# XE167FM.net
KiCad netlist of a schematic drawn in EAGLE
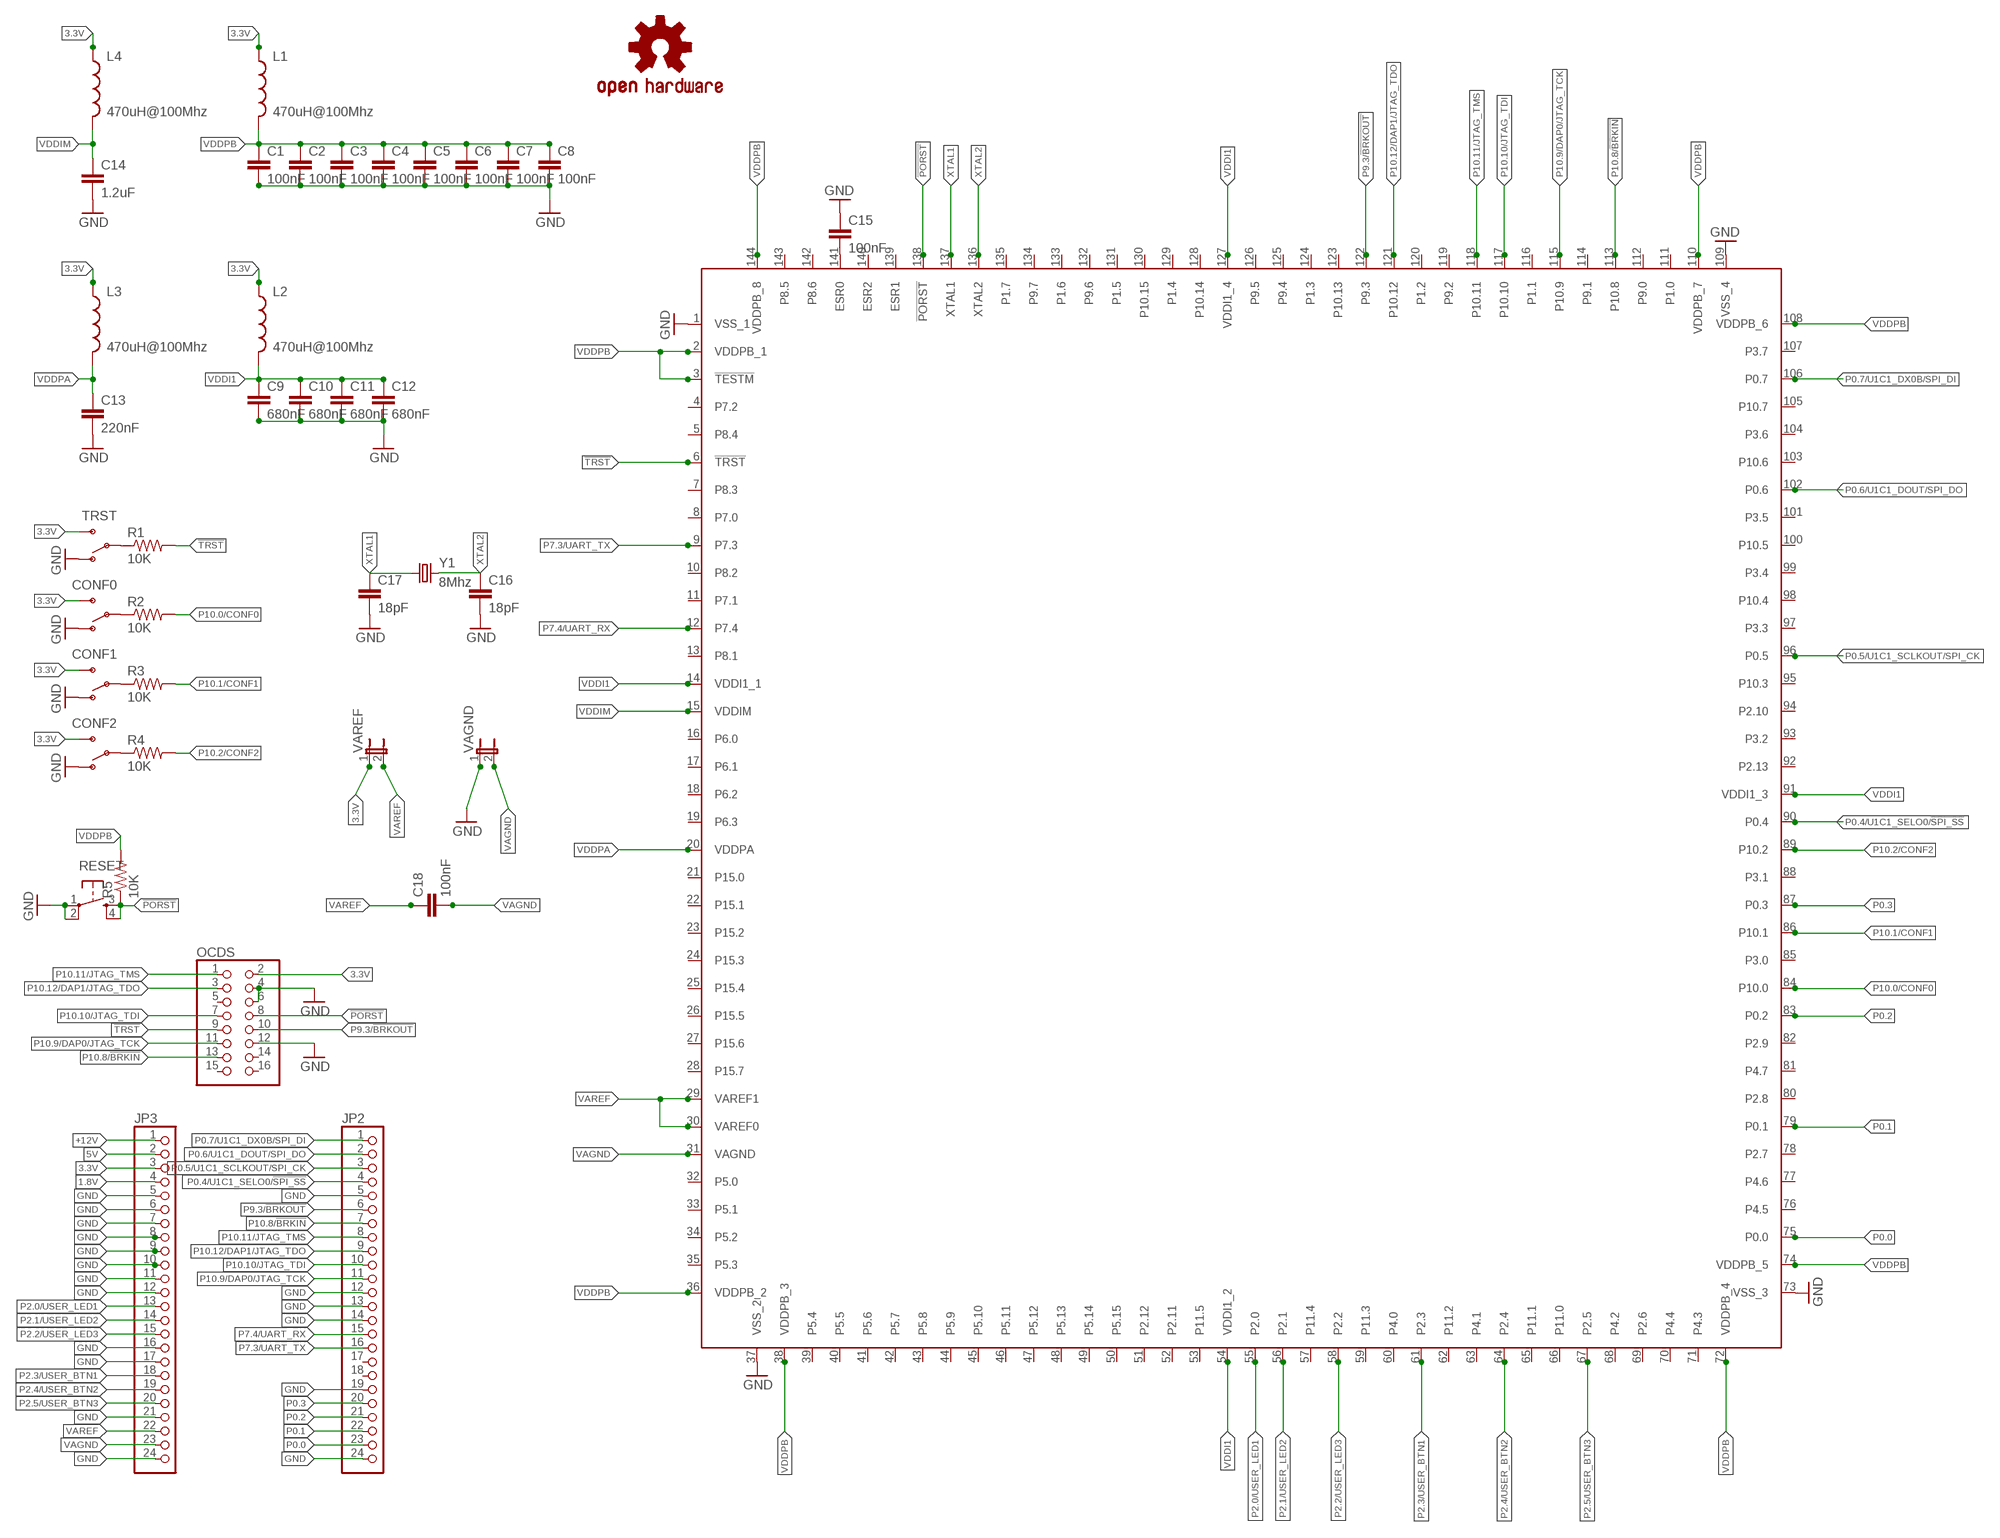
[diagram p0: schematic, sheet 1]

(export (version "E")
  (design (tool "Eeschema 10.0.6"))
  (components
    (comp (ref "C1")
      (value "100nF")
      (footprint "eagle-import:0603-CAP")
      (libsource (lib "eagle-import") (part "CAP0603-CAP"))
    )
    (comp (ref "C2")
      (value "100nF")
      (footprint "eagle-import:0603-CAP")
      (libsource (lib "eagle-import") (part "CAP0603-CAP"))
    )
    (comp (ref "C3")
      (value "100nF")
      (footprint "eagle-import:0603-CAP")
      (libsource (lib "eagle-import") (part "CAP0603-CAP"))
    )
    (comp (ref "C4")
      (value "100nF")
      (footprint "eagle-import:0603-CAP")
      (libsource (lib "eagle-import") (part "CAP0603-CAP"))
    )
    (comp (ref "C5")
      (value "100nF")
      (footprint "eagle-import:0603-CAP")
      (libsource (lib "eagle-import") (part "CAP0603-CAP"))
    )
    (comp (ref "C6")
      (value "100nF")
      (footprint "eagle-import:0603-CAP")
      (libsource (lib "eagle-import") (part "CAP0603-CAP"))
    )
    (comp (ref "C7")
      (value "100nF")
      (footprint "eagle-import:0603-CAP")
      (libsource (lib "eagle-import") (part "CAP0603-CAP"))
    )
    (comp (ref "C8")
      (value "100nF")
      (footprint "eagle-import:0603-CAP")
      (libsource (lib "eagle-import") (part "CAP0603-CAP"))
    )
    (comp (ref "C9")
      (value "680nF")
      (footprint "eagle-import:0603-CAP")
      (libsource (lib "eagle-import") (part "CAP0603-CAP"))
    )
    (comp (ref "C10")
      (value "680nF")
      (footprint "eagle-import:0603-CAP")
      (libsource (lib "eagle-import") (part "CAP0603-CAP"))
    )
    (comp (ref "C11")
      (value "680nF")
      (footprint "eagle-import:0603-CAP")
      (libsource (lib "eagle-import") (part "CAP0603-CAP"))
    )
    (comp (ref "C12")
      (value "680nF")
      (footprint "eagle-import:0603-CAP")
      (libsource (lib "eagle-import") (part "CAP0603-CAP"))
    )
    (comp (ref "C13")
      (value "220nF")
      (footprint "eagle-import:0603-CAP")
      (libsource (lib "eagle-import") (part "CAP0603-CAP"))
    )
    (comp (ref "C14")
      (value "1.2uF")
      (footprint "eagle-import:0603-CAP")
      (libsource (lib "eagle-import") (part "CAP0603-CAP"))
    )
    (comp (ref "C15")
      (value "100nF")
      (footprint "eagle-import:0603-CAP")
      (libsource (lib "eagle-import") (part "CAP0603-CAP"))
    )
    (comp (ref "C16")
      (value "18pF")
      (footprint "eagle-import:0603-CAP")
      (libsource (lib "eagle-import") (part "CAP0603-CAP"))
    )
    (comp (ref "C17")
      (value "18pF")
      (footprint "eagle-import:0603-CAP")
      (libsource (lib "eagle-import") (part "CAP0603-CAP"))
    )
    (comp (ref "C18")
      (value "100nF")
      (footprint "eagle-import:0603-CAP")
      (libsource (lib "eagle-import") (part "CAP0603-CAP"))
    )
    (comp (ref "CONF0")
      (value "SWITCH-SPDTPTH")
      (footprint "eagle-import:SWITCH-SPDT")
      (libsource (lib "eagle-import") (part "SWITCH-SPDTPTH"))
    )
    (comp (ref "CONF1")
      (value "SWITCH-SPDTPTH")
      (footprint "eagle-import:SWITCH-SPDT")
      (libsource (lib "eagle-import") (part "SWITCH-SPDTPTH"))
    )
    (comp (ref "CONF2")
      (value "SWITCH-SPDTPTH")
      (footprint "eagle-import:SWITCH-SPDT")
      (libsource (lib "eagle-import") (part "SWITCH-SPDTPTH"))
    )
    (comp (ref "IC1")
      (value "XE167FM")
      (footprint "eagle-import:LQFP144")
      (libsource (lib "eagle-import") (part "XE167FM"))
    )
    (comp (ref "JP2")
      (value "PINHD-1X24")
      (footprint "eagle-import:1X24")
      (libsource (lib "eagle-import") (part "PINHD-1X24"))
    )
    (comp (ref "JP3")
      (value "PINHD-1X24")
      (footprint "eagle-import:1X24")
      (libsource (lib "eagle-import") (part "PINHD-1X24"))
    )
    (comp (ref "L1")
      (value "470uH@100Mhz")
      (footprint "eagle-import:0603")
      (libsource (lib "eagle-import") (part "INDUCTOR0603"))
    )
    (comp (ref "L2")
      (value "470uH@100Mhz")
      (footprint "eagle-import:0603")
      (libsource (lib "eagle-import") (part "INDUCTOR0603"))
    )
    (comp (ref "L3")
      (value "470uH@100Mhz")
      (footprint "eagle-import:0603")
      (libsource (lib "eagle-import") (part "INDUCTOR0603"))
    )
    (comp (ref "L4")
      (value "470uH@100Mhz")
      (footprint "eagle-import:0603")
      (libsource (lib "eagle-import") (part "INDUCTOR0603"))
    )
    (comp (ref "LOGO1")
      (value "OSHW-LOGOS")
      (footprint "eagle-import:OSHW-LOGO-S")
      (libsource (lib "eagle-import") (part "OSHW-LOGOS"))
    )
    (comp (ref "OCDS")
      (value "PINHD-2X8_2.54")
      (footprint "eagle-import:2X08")
      (libsource (lib "eagle-import") (part "PINHD-2X8_2.54"))
    )
    (comp (ref "R1")
      (value "10K")
      (footprint "eagle-import:0603-RES")
      (libsource (lib "eagle-import") (part "RESISTOR0603-RES"))
    )
    (comp (ref "R2")
      (value "10K")
      (footprint "eagle-import:0603-RES")
      (libsource (lib "eagle-import") (part "RESISTOR0603-RES"))
    )
    (comp (ref "R3")
      (value "10K")
      (footprint "eagle-import:0603-RES")
      (libsource (lib "eagle-import") (part "RESISTOR0603-RES"))
    )
    (comp (ref "R4")
      (value "10K")
      (footprint "eagle-import:0603-RES")
      (libsource (lib "eagle-import") (part "RESISTOR0603-RES"))
    )
    (comp (ref "R5")
      (value "10K")
      (footprint "eagle-import:0603-RES")
      (libsource (lib "eagle-import") (part "RESISTOR0603-RES"))
    )
    (comp (ref "RESET")
      (value "TAC_SWITCHPTH")
      (footprint "eagle-import:TACTILE-PTH")
      (libsource (lib "eagle-import") (part "TAC_SWITCHPTH"))
    )
    (comp (ref "TRST")
      (value "SWITCH-SPDTPTH")
      (footprint "eagle-import:SWITCH-SPDT")
      (libsource (lib "eagle-import") (part "SWITCH-SPDTPTH"))
    )
    (comp (ref "VAGND")
      (value "JP1E")
      (footprint "eagle-import:JP1")
      (libsource (lib "eagle-import") (part "JP1E"))
    )
    (comp (ref "VAREF")
      (value "JP1E")
      (footprint "eagle-import:JP1")
      (libsource (lib "eagle-import") (part "JP1E"))
    )
    (comp (ref "Y1")
      (value "8Mhz")
      (footprint "eagle-import:HC49UP")
      (libsource (lib "eagle-import") (part "CRYSTALSMD"))
    )
  )
  (nets
    (net (code "1") (name "+12V") (class "Default")
      (node (ref "JP3") (pin "1") (pinfunction "1_1") (pintype "passive"))
    )
    (net (code "2") (name "/P0.4{slash}U1C1_SELO0{slash}~{SPI_SS}") (class "Default")
      (node (ref "IC1") (pin "90") (pinfunction "P0.4_90") (pintype "passive"))
      (node (ref "JP2") (pin "4") (pinfunction "4_4") (pintype "passive"))
    )
    (net (code "3") (name "/P9.3{slash}~{BRKOUT}") (class "Default")
      (node (ref "IC1") (pin "122") (pinfunction "P9.3_122") (pintype "passive"))
      (node (ref "JP2") (pin "6") (pinfunction "6_6") (pintype "passive"))
      (node (ref "OCDS") (pin "10") (pinfunction "10_10") (pintype "passive"))
    )
    (net (code "4") (name "/P10.8{slash}~{BRKIN}") (class "Default")
      (node (ref "IC1") (pin "113") (pinfunction "P10.8_113") (pintype "passive"))
      (node (ref "JP2") (pin "7") (pinfunction "7_7") (pintype "passive"))
      (node (ref "OCDS") (pin "13") (pinfunction "13_13") (pintype "passive"))
    )
    (net (code "5") (name "/~{PORST}") (class "Default")
      (node (ref "IC1") (pin "138") (pinfunction "~{PORST}_138") (pintype "passive"))
      (node (ref "OCDS") (pin "8") (pinfunction "8_8") (pintype "passive"))
      (node (ref "R5") (pin "1") (pinfunction "1_1") (pintype "passive"))
      (node (ref "RESET") (pin "3") (pinfunction "3_3") (pintype "passive"))
      (node (ref "RESET") (pin "4") (pinfunction "4_4") (pintype "passive"))
    )
    (net (code "6") (name "/~{TRST}") (class "Default")
      (node (ref "IC1") (pin "6") (pinfunction "~{TRST}_6") (pintype "passive"))
      (node (ref "OCDS") (pin "9") (pinfunction "9_9") (pintype "passive"))
      (node (ref "R1") (pin "2") (pinfunction "2_2") (pintype "passive"))
    )
    (net (code "7") (name "1.8V") (class "Default")
      (node (ref "JP3") (pin "4") (pinfunction "4_4") (pintype "passive"))
    )
    (net (code "8") (name "3.3V") (class "Default")
      (node (ref "CONF0") (pin "3") (pinfunction "S_3") (pintype "passive"))
      (node (ref "CONF1") (pin "3") (pinfunction "S_3") (pintype "passive"))
      (node (ref "CONF2") (pin "3") (pinfunction "S_3") (pintype "passive"))
      (node (ref "JP3") (pin "3") (pinfunction "3_3") (pintype "passive"))
      (node (ref "L1") (pin "1") (pinfunction "1_1") (pintype "passive"))
      (node (ref "L2") (pin "1") (pinfunction "1_1") (pintype "passive"))
      (node (ref "L3") (pin "1") (pinfunction "1_1") (pintype "passive"))
      (node (ref "L4") (pin "1") (pinfunction "1_1") (pintype "passive"))
      (node (ref "OCDS") (pin "2") (pinfunction "2_2") (pintype "passive"))
      (node (ref "TRST") (pin "3") (pinfunction "S_3") (pintype "passive"))
      (node (ref "VAREF") (pin "1") (pinfunction "1_1") (pintype "passive"))
    )
    (net (code "9") (name "5V") (class "Default")
      (node (ref "JP3") (pin "2") (pinfunction "2_2") (pintype "passive"))
    )
    (net (code "10") (name "GND") (class "Default")
      (node (ref "C1") (pin "2") (pinfunction "2_2") (pintype "passive"))
      (node (ref "C10") (pin "2") (pinfunction "2_2") (pintype "passive"))
      (node (ref "C11") (pin "2") (pinfunction "2_2") (pintype "passive"))
      (node (ref "C12") (pin "2") (pinfunction "2_2") (pintype "passive"))
      (node (ref "C13") (pin "2") (pinfunction "2_2") (pintype "passive"))
      (node (ref "C14") (pin "2") (pinfunction "2_2") (pintype "passive"))
      (node (ref "C15") (pin "1") (pinfunction "1_1") (pintype "passive"))
      (node (ref "C16") (pin "2") (pinfunction "2_2") (pintype "passive"))
      (node (ref "C17") (pin "2") (pinfunction "2_2") (pintype "passive"))
      (node (ref "C2") (pin "2") (pinfunction "2_2") (pintype "passive"))
      (node (ref "C3") (pin "2") (pinfunction "2_2") (pintype "passive"))
      (node (ref "C4") (pin "2") (pinfunction "2_2") (pintype "passive"))
      (node (ref "C5") (pin "2") (pinfunction "2_2") (pintype "passive"))
      (node (ref "C6") (pin "2") (pinfunction "2_2") (pintype "passive"))
      (node (ref "C7") (pin "2") (pinfunction "2_2") (pintype "passive"))
      (node (ref "C8") (pin "2") (pinfunction "2_2") (pintype "passive"))
      (node (ref "C9") (pin "2") (pinfunction "2_2") (pintype "passive"))
      (node (ref "CONF0") (pin "1") (pinfunction "O_1") (pintype "passive"))
      (node (ref "CONF1") (pin "1") (pinfunction "O_1") (pintype "passive"))
      (node (ref "CONF2") (pin "1") (pinfunction "O_1") (pintype "passive"))
      (node (ref "IC1") (pin "1") (pinfunction "VSS_1_1") (pintype "passive"))
      (node (ref "IC1") (pin "109") (pinfunction "VSS_4_109") (pintype "passive"))
      (node (ref "IC1") (pin "37") (pinfunction "VSS_2_37") (pintype "passive"))
      (node (ref "IC1") (pin "73") (pinfunction "VSS_3_73") (pintype "passive"))
      (node (ref "JP2") (pin "12") (pinfunction "12_12") (pintype "passive"))
      (node (ref "JP2") (pin "13") (pinfunction "13_13") (pintype "passive"))
      (node (ref "JP2") (pin "14") (pinfunction "14_14") (pintype "passive"))
      (node (ref "JP2") (pin "19") (pinfunction "19_19") (pintype "passive"))
      (node (ref "JP2") (pin "24") (pinfunction "24_24") (pintype "passive"))
      (node (ref "JP2") (pin "5") (pinfunction "5_5") (pintype "passive"))
      (node (ref "JP3") (pin "10") (pinfunction "10_10") (pintype "passive"))
      (node (ref "JP3") (pin "11") (pinfunction "11_11") (pintype "passive"))
      (node (ref "JP3") (pin "12") (pinfunction "12_12") (pintype "passive"))
      (node (ref "JP3") (pin "16") (pinfunction "16_16") (pintype "passive"))
      (node (ref "JP3") (pin "17") (pinfunction "17_17") (pintype "passive"))
      (node (ref "JP3") (pin "21") (pinfunction "21_21") (pintype "passive"))
      (node (ref "JP3") (pin "24") (pinfunction "24_24") (pintype "passive"))
      (node (ref "JP3") (pin "5") (pinfunction "5_5") (pintype "passive"))
      (node (ref "JP3") (pin "6") (pinfunction "6_6") (pintype "passive"))
      (node (ref "JP3") (pin "7") (pinfunction "7_7") (pintype "passive"))
      (node (ref "JP3") (pin "8") (pinfunction "8_8") (pintype "passive"))
      (node (ref "JP3") (pin "9") (pinfunction "9_9") (pintype "passive"))
      (node (ref "OCDS") (pin "12") (pinfunction "12_12") (pintype "passive"))
      (node (ref "OCDS") (pin "4") (pinfunction "4_4") (pintype "passive"))
      (node (ref "OCDS") (pin "6") (pinfunction "6_6") (pintype "passive"))
      (node (ref "RESET") (pin "1") (pinfunction "1_1") (pintype "passive"))
      (node (ref "RESET") (pin "2") (pinfunction "2_2") (pintype "passive"))
      (node (ref "TRST") (pin "1") (pinfunction "O_1") (pintype "passive"))
      (node (ref "VAGND") (pin "1") (pinfunction "1_1") (pintype "passive"))
    )
    (net (code "11") (name "Net-(CONF0-P)") (class "Default")
      (node (ref "CONF0") (pin "2") (pinfunction "P_2") (pintype "passive"))
      (node (ref "R2") (pin "1") (pinfunction "1_1") (pintype "passive"))
    )
    (net (code "12") (name "Net-(CONF1-P)") (class "Default")
      (node (ref "CONF1") (pin "2") (pinfunction "P_2") (pintype "passive"))
      (node (ref "R3") (pin "1") (pinfunction "1_1") (pintype "passive"))
    )
    (net (code "13") (name "Net-(CONF2-P)") (class "Default")
      (node (ref "CONF2") (pin "2") (pinfunction "P_2") (pintype "passive"))
      (node (ref "R4") (pin "1") (pinfunction "1_1") (pintype "passive"))
    )
    (net (code "14") (name "Net-(IC1-ESR0)") (class "Default")
      (node (ref "C15") (pin "2") (pinfunction "2_2") (pintype "passive"))
      (node (ref "IC1") (pin "141") (pinfunction "ESR0_141") (pintype "passive"))
    )
    (net (code "15") (name "Net-(TRST-P)") (class "Default")
      (node (ref "R1") (pin "1") (pinfunction "1_1") (pintype "passive"))
      (node (ref "TRST") (pin "2") (pinfunction "P_2") (pintype "passive"))
    )
    (net (code "16") (name "P0.0") (class "Default")
      (node (ref "IC1") (pin "75") (pinfunction "P0.0_75") (pintype "passive"))
      (node (ref "JP2") (pin "23") (pinfunction "23_23") (pintype "passive"))
    )
    (net (code "17") (name "P0.1") (class "Default")
      (node (ref "IC1") (pin "79") (pinfunction "P0.1_79") (pintype "passive"))
      (node (ref "JP2") (pin "22") (pinfunction "22_22") (pintype "passive"))
    )
    (net (code "18") (name "P0.2") (class "Default")
      (node (ref "IC1") (pin "83") (pinfunction "P0.2_83") (pintype "passive"))
      (node (ref "JP2") (pin "21") (pinfunction "21_21") (pintype "passive"))
    )
    (net (code "19") (name "P0.3") (class "Default")
      (node (ref "IC1") (pin "87") (pinfunction "P0.3_87") (pintype "passive"))
      (node (ref "JP2") (pin "20") (pinfunction "20_20") (pintype "passive"))
    )
    (net (code "20") (name "P0.5{slash}U1C1_SCLKOUT{slash}SPI_CK") (class "Default")
      (node (ref "IC1") (pin "96") (pinfunction "P0.5_96") (pintype "passive"))
      (node (ref "JP2") (pin "3") (pinfunction "3_3") (pintype "passive"))
    )
    (net (code "21") (name "P0.6{slash}U1C1_DOUT{slash}SPI_DO") (class "Default")
      (node (ref "IC1") (pin "102") (pinfunction "P0.6_102") (pintype "passive"))
      (node (ref "JP2") (pin "2") (pinfunction "2_2") (pintype "passive"))
    )
    (net (code "22") (name "P0.7{slash}U1C1_DX0B{slash}SPI_DI") (class "Default")
      (node (ref "IC1") (pin "106") (pinfunction "P0.7_106") (pintype "passive"))
      (node (ref "JP2") (pin "1") (pinfunction "1_1") (pintype "passive"))
    )
    (net (code "23") (name "P2.0{slash}USER_LED1") (class "Default")
      (node (ref "IC1") (pin "55") (pinfunction "P2.0_55") (pintype "passive"))
      (node (ref "JP3") (pin "13") (pinfunction "13_13") (pintype "passive"))
    )
    (net (code "24") (name "P2.1{slash}USER_LED2") (class "Default")
      (node (ref "IC1") (pin "56") (pinfunction "P2.1_56") (pintype "passive"))
      (node (ref "JP3") (pin "14") (pinfunction "14_14") (pintype "passive"))
    )
    (net (code "25") (name "P2.2{slash}USER_LED3") (class "Default")
      (node (ref "IC1") (pin "58") (pinfunction "P2.2_58") (pintype "passive"))
      (node (ref "JP3") (pin "15") (pinfunction "15_15") (pintype "passive"))
    )
    (net (code "26") (name "P2.3{slash}USER_BTN1") (class "Default")
      (node (ref "IC1") (pin "61") (pinfunction "P2.3_61") (pintype "passive"))
      (node (ref "JP3") (pin "18") (pinfunction "18_18") (pintype "passive"))
    )
    (net (code "27") (name "P2.4{slash}USER_BTN2") (class "Default")
      (node (ref "IC1") (pin "64") (pinfunction "P2.4_64") (pintype "passive"))
      (node (ref "JP3") (pin "19") (pinfunction "19_19") (pintype "passive"))
    )
    (net (code "28") (name "P2.5{slash}USER_BTN3") (class "Default")
      (node (ref "IC1") (pin "67") (pinfunction "P2.5_67") (pintype "passive"))
      (node (ref "JP3") (pin "20") (pinfunction "20_20") (pintype "passive"))
    )
    (net (code "29") (name "P7.3{slash}UART_TX") (class "Default")
      (node (ref "IC1") (pin "9") (pinfunction "P7.3_9") (pintype "passive"))
      (node (ref "JP2") (pin "16") (pinfunction "16_16") (pintype "passive"))
    )
    (net (code "30") (name "P7.4{slash}UART_RX") (class "Default")
      (node (ref "IC1") (pin "12") (pinfunction "P7.4_12") (pintype "passive"))
      (node (ref "JP2") (pin "15") (pinfunction "15_15") (pintype "passive"))
    )
    (net (code "31") (name "P10.0{slash}CONF0") (class "Default")
      (node (ref "IC1") (pin "84") (pinfunction "P10.0_84") (pintype "passive"))
      (node (ref "R2") (pin "2") (pinfunction "2_2") (pintype "passive"))
    )
    (net (code "32") (name "P10.1{slash}CONF1") (class "Default")
      (node (ref "IC1") (pin "86") (pinfunction "P10.1_86") (pintype "passive"))
      (node (ref "R3") (pin "2") (pinfunction "2_2") (pintype "passive"))
    )
    (net (code "33") (name "P10.2{slash}CONF2") (class "Default")
      (node (ref "IC1") (pin "89") (pinfunction "P10.2_89") (pintype "passive"))
      (node (ref "R4") (pin "2") (pinfunction "2_2") (pintype "passive"))
    )
    (net (code "34") (name "P10.9{slash}DAP0{slash}JTAG_TCK") (class "Default")
      (node (ref "IC1") (pin "115") (pinfunction "P10.9_115") (pintype "passive"))
      (node (ref "JP2") (pin "11") (pinfunction "11_11") (pintype "passive"))
      (node (ref "OCDS") (pin "11") (pinfunction "11_11") (pintype "passive"))
    )
    (net (code "35") (name "P10.10{slash}JTAG_TDI") (class "Default")
      (node (ref "IC1") (pin "117") (pinfunction "P10.10_117") (pintype "passive"))
      (node (ref "JP2") (pin "10") (pinfunction "10_10") (pintype "passive"))
      (node (ref "OCDS") (pin "7") (pinfunction "7_7") (pintype "passive"))
    )
    (net (code "36") (name "P10.11{slash}JTAG_TMS") (class "Default")
      (node (ref "IC1") (pin "118") (pinfunction "P10.11_118") (pintype "passive"))
      (node (ref "JP2") (pin "8") (pinfunction "8_8") (pintype "passive"))
      (node (ref "OCDS") (pin "1") (pinfunction "1_1") (pintype "passive"))
    )
    (net (code "37") (name "P10.12{slash}DAP1{slash}JTAG_TDO") (class "Default")
      (node (ref "IC1") (pin "121") (pinfunction "P10.12_121") (pintype "passive"))
      (node (ref "JP2") (pin "9") (pinfunction "9_9") (pintype "passive"))
      (node (ref "OCDS") (pin "3") (pinfunction "3_3") (pintype "passive"))
    )
    (net (code "38") (name "VAGND") (class "Default")
      (node (ref "C18") (pin "2") (pinfunction "2_2") (pintype "passive"))
      (node (ref "IC1") (pin "31") (pinfunction "VAGND_31") (pintype "passive"))
      (node (ref "JP3") (pin "23") (pinfunction "23_23") (pintype "passive"))
      (node (ref "VAGND") (pin "2") (pinfunction "2_2") (pintype "passive"))
    )
    (net (code "39") (name "VAREF") (class "Default")
      (node (ref "C18") (pin "1") (pinfunction "1_1") (pintype "passive"))
      (node (ref "IC1") (pin "29") (pinfunction "VAREF1_29") (pintype "passive"))
      (node (ref "IC1") (pin "30") (pinfunction "VAREF0_30") (pintype "passive"))
      (node (ref "JP3") (pin "22") (pinfunction "22_22") (pintype "passive"))
      (node (ref "VAREF") (pin "2") (pinfunction "2_2") (pintype "passive"))
    )
    (net (code "40") (name "VDDI1") (class "Default")
      (node (ref "C10") (pin "1") (pinfunction "1_1") (pintype "passive"))
      (node (ref "C11") (pin "1") (pinfunction "1_1") (pintype "passive"))
      (node (ref "C12") (pin "1") (pinfunction "1_1") (pintype "passive"))
      (node (ref "C9") (pin "1") (pinfunction "1_1") (pintype "passive"))
      (node (ref "IC1") (pin "127") (pinfunction "VDDI1_4_127") (pintype "passive"))
      (node (ref "IC1") (pin "14") (pinfunction "VDDI1_1_14") (pintype "passive"))
      (node (ref "IC1") (pin "54") (pinfunction "VDDI1_2_54") (pintype "passive"))
      (node (ref "IC1") (pin "91") (pinfunction "VDDI1_3_91") (pintype "passive"))
      (node (ref "L2") (pin "2") (pinfunction "2_2") (pintype "passive"))
    )
    (net (code "41") (name "VDDIM") (class "Default")
      (node (ref "C14") (pin "1") (pinfunction "1_1") (pintype "passive"))
      (node (ref "IC1") (pin "15") (pinfunction "VDDIM_15") (pintype "passive"))
      (node (ref "L4") (pin "2") (pinfunction "2_2") (pintype "passive"))
    )
    (net (code "42") (name "VDDPA") (class "Default")
      (node (ref "C13") (pin "1") (pinfunction "1_1") (pintype "passive"))
      (node (ref "IC1") (pin "20") (pinfunction "VDDPA_20") (pintype "passive"))
      (node (ref "L3") (pin "2") (pinfunction "2_2") (pintype "passive"))
    )
    (net (code "43") (name "VDDPB") (class "Default")
      (node (ref "C1") (pin "1") (pinfunction "1_1") (pintype "passive"))
      (node (ref "C2") (pin "1") (pinfunction "1_1") (pintype "passive"))
      (node (ref "C3") (pin "1") (pinfunction "1_1") (pintype "passive"))
      (node (ref "C4") (pin "1") (pinfunction "1_1") (pintype "passive"))
      (node (ref "C5") (pin "1") (pinfunction "1_1") (pintype "passive"))
      (node (ref "C6") (pin "1") (pinfunction "1_1") (pintype "passive"))
      (node (ref "C7") (pin "1") (pinfunction "1_1") (pintype "passive"))
      (node (ref "C8") (pin "1") (pinfunction "1_1") (pintype "passive"))
      (node (ref "IC1") (pin "108") (pinfunction "VDDPB_6_108") (pintype "passive"))
      (node (ref "IC1") (pin "110") (pinfunction "VDDPB_7_110") (pintype "passive"))
      (node (ref "IC1") (pin "144") (pinfunction "VDDPB_8_144") (pintype "passive"))
      (node (ref "IC1") (pin "2") (pinfunction "VDDPB_1_2") (pintype "passive"))
      (node (ref "IC1") (pin "3") (pinfunction "~{TESTM}_3") (pintype "passive"))
      (node (ref "IC1") (pin "36") (pinfunction "VDDPB_2_36") (pintype "passive"))
      (node (ref "IC1") (pin "38") (pinfunction "VDDPB_3_38") (pintype "passive"))
      (node (ref "IC1") (pin "72") (pinfunction "VDDPB_4_72") (pintype "passive"))
      (node (ref "IC1") (pin "74") (pinfunction "VDDPB_5_74") (pintype "passive"))
      (node (ref "L1") (pin "2") (pinfunction "2_2") (pintype "passive"))
      (node (ref "R5") (pin "2") (pinfunction "2_2") (pintype "passive"))
    )
    (net (code "44") (name "XTAL1") (class "Default")
      (node (ref "C17") (pin "1") (pinfunction "1_1") (pintype "passive"))
      (node (ref "IC1") (pin "137") (pinfunction "XTAL1_137") (pintype "passive"))
      (node (ref "Y1") (pin "1") (pinfunction "1_1") (pintype "passive"))
    )
    (net (code "45") (name "XTAL2") (class "Default")
      (node (ref "C16") (pin "1") (pinfunction "1_1") (pintype "passive"))
      (node (ref "IC1") (pin "136") (pinfunction "XTAL2_136") (pintype "passive"))
      (node (ref "Y1") (pin "2") (pinfunction "2_2") (pintype "passive"))
    )
    (net (code "46") (name "unconnected-(IC1-ESR1-Pad139)") (class "Default")
      (node (ref "IC1") (pin "139") (pinfunction "ESR1_139") (pintype "passive"))
    )
    (net (code "47") (name "unconnected-(IC1-ESR2-Pad140)") (class "Default")
      (node (ref "IC1") (pin "140") (pinfunction "ESR2_140") (pintype "passive"))
    )
    (net (code "48") (name "unconnected-(IC1-P1.0-Pad111)") (class "Default")
      (node (ref "IC1") (pin "111") (pinfunction "P1.0_111") (pintype "passive"))
    )
    (net (code "49") (name "unconnected-(IC1-P1.1-Pad116)") (class "Default")
      (node (ref "IC1") (pin "116") (pinfunction "P1.1_116") (pintype "passive"))
    )
    (net (code "50") (name "unconnected-(IC1-P1.2-Pad120)") (class "Default")
      (node (ref "IC1") (pin "120") (pinfunction "P1.2_120") (pintype "passive"))
    )
    (net (code "51") (name "unconnected-(IC1-P1.3-Pad124)") (class "Default")
      (node (ref "IC1") (pin "124") (pinfunction "P1.3_124") (pintype "passive"))
    )
    (net (code "52") (name "unconnected-(IC1-P1.4-Pad129)") (class "Default")
      (node (ref "IC1") (pin "129") (pinfunction "P1.4_129") (pintype "passive"))
    )
    (net (code "53") (name "unconnected-(IC1-P1.5-Pad131)") (class "Default")
      (node (ref "IC1") (pin "131") (pinfunction "P1.5_131") (pintype "passive"))
    )
    (net (code "54") (name "unconnected-(IC1-P1.6-Pad133)") (class "Default")
      (node (ref "IC1") (pin "133") (pinfunction "P1.6_133") (pintype "passive"))
    )
    (net (code "55") (name "unconnected-(IC1-P1.7-Pad135)") (class "Default")
      (node (ref "IC1") (pin "135") (pinfunction "P1.7_135") (pintype "passive"))
    )
    (net (code "56") (name "unconnected-(IC1-P2.6-Pad69)") (class "Default")
      (node (ref "IC1") (pin "69") (pinfunction "P2.6_69") (pintype "passive"))
    )
    (net (code "57") (name "unconnected-(IC1-P2.7-Pad78)") (class "Default")
      (node (ref "IC1") (pin "78") (pinfunction "P2.7_78") (pintype "passive"))
    )
    (net (code "58") (name "unconnected-(IC1-P2.8-Pad80)") (class "Default")
      (node (ref "IC1") (pin "80") (pinfunction "P2.8_80") (pintype "passive"))
    )
    (net (code "59") (name "unconnected-(IC1-P2.9-Pad82)") (class "Default")
      (node (ref "IC1") (pin "82") (pinfunction "P2.9_82") (pintype "passive"))
    )
    (net (code "60") (name "unconnected-(IC1-P2.10-Pad94)") (class "Default")
      (node (ref "IC1") (pin "94") (pinfunction "P2.10_94") (pintype "passive"))
    )
    (net (code "61") (name "unconnected-(IC1-P2.11-Pad52)") (class "Default")
      (node (ref "IC1") (pin "52") (pinfunction "P2.11_52") (pintype "passive"))
    )
    (net (code "62") (name "unconnected-(IC1-P2.12-Pad51)") (class "Default")
      (node (ref "IC1") (pin "51") (pinfunction "P2.12_51") (pintype "passive"))
    )
    (net (code "63") (name "unconnected-(IC1-P2.13-Pad92)") (class "Default")
      (node (ref "IC1") (pin "92") (pinfunction "P2.13_92") (pintype "passive"))
    )
    (net (code "64") (name "unconnected-(IC1-P3.0-Pad85)") (class "Default")
      (node (ref "IC1") (pin "85") (pinfunction "P3.0_85") (pintype "passive"))
    )
    (net (code "65") (name "unconnected-(IC1-P3.1-Pad88)") (class "Default")
      (node (ref "IC1") (pin "88") (pinfunction "P3.1_88") (pintype "passive"))
    )
    (net (code "66") (name "unconnected-(IC1-P3.2-Pad93)") (class "Default")
      (node (ref "IC1") (pin "93") (pinfunction "P3.2_93") (pintype "passive"))
    )
    (net (code "67") (name "unconnected-(IC1-P3.3-Pad97)") (class "Default")
      (node (ref "IC1") (pin "97") (pinfunction "P3.3_97") (pintype "passive"))
    )
    (net (code "68") (name "unconnected-(IC1-P3.4-Pad99)") (class "Default")
      (node (ref "IC1") (pin "99") (pinfunction "P3.4_99") (pintype "passive"))
    )
    (net (code "69") (name "unconnected-(IC1-P3.5-Pad101)") (class "Default")
      (node (ref "IC1") (pin "101") (pinfunction "P3.5_101") (pintype "passive"))
    )
    (net (code "70") (name "unconnected-(IC1-P3.6-Pad104)") (class "Default")
      (node (ref "IC1") (pin "104") (pinfunction "P3.6_104") (pintype "passive"))
    )
    (net (code "71") (name "unconnected-(IC1-P3.7-Pad107)") (class "Default")
      (node (ref "IC1") (pin "107") (pinfunction "P3.7_107") (pintype "passive"))
    )
    (net (code "72") (name "unconnected-(IC1-P4.0-Pad60)") (class "Default")
      (node (ref "IC1") (pin "60") (pinfunction "P4.0_60") (pintype "passive"))
    )
    (net (code "73") (name "unconnected-(IC1-P4.1-Pad63)") (class "Default")
      (node (ref "IC1") (pin "63") (pinfunction "P4.1_63") (pintype "passive"))
    )
    (net (code "74") (name "unconnected-(IC1-P4.2-Pad68)") (class "Default")
      (node (ref "IC1") (pin "68") (pinfunction "P4.2_68") (pintype "passive"))
    )
    (net (code "75") (name "unconnected-(IC1-P4.3-Pad71)") (class "Default")
      (node (ref "IC1") (pin "71") (pinfunction "P4.3_71") (pintype "passive"))
    )
    (net (code "76") (name "unconnected-(IC1-P4.4-Pad70)") (class "Default")
      (node (ref "IC1") (pin "70") (pinfunction "P4.4_70") (pintype "passive"))
    )
    (net (code "77") (name "unconnected-(IC1-P4.5-Pad76)") (class "Default")
      (node (ref "IC1") (pin "76") (pinfunction "P4.5_76") (pintype "passive"))
    )
    (net (code "78") (name "unconnected-(IC1-P4.6-Pad77)") (class "Default")
      (node (ref "IC1") (pin "77") (pinfunction "P4.6_77") (pintype "passive"))
    )
    (net (code "79") (name "unconnected-(IC1-P4.7-Pad81)") (class "Default")
      (node (ref "IC1") (pin "81") (pinfunction "P4.7_81") (pintype "passive"))
    )
    (net (code "80") (name "unconnected-(IC1-P5.0-Pad32)") (class "Default")
      (node (ref "IC1") (pin "32") (pinfunction "P5.0_32") (pintype "passive"))
    )
    (net (code "81") (name "unconnected-(IC1-P5.1-Pad33)") (class "Default")
      (node (ref "IC1") (pin "33") (pinfunction "P5.1_33") (pintype "passive"))
    )
    (net (code "82") (name "unconnected-(IC1-P5.2-Pad34)") (class "Default")
      (node (ref "IC1") (pin "34") (pinfunction "P5.2_34") (pintype "passive"))
    )
    (net (code "83") (name "unconnected-(IC1-P5.3-Pad35)") (class "Default")
      (node (ref "IC1") (pin "35") (pinfunction "P5.3_35") (pintype "passive"))
    )
    (net (code "84") (name "unconnected-(IC1-P5.4-Pad39)") (class "Default")
      (node (ref "IC1") (pin "39") (pinfunction "P5.4_39") (pintype "passive"))
    )
    (net (code "85") (name "unconnected-(IC1-P5.5-Pad40)") (class "Default")
      (node (ref "IC1") (pin "40") (pinfunction "P5.5_40") (pintype "passive"))
    )
    (net (code "86") (name "unconnected-(IC1-P5.6-Pad41)") (class "Default")
      (node (ref "IC1") (pin "41") (pinfunction "P5.6_41") (pintype "passive"))
    )
    (net (code "87") (name "unconnected-(IC1-P5.7-Pad42)") (class "Default")
      (node (ref "IC1") (pin "42") (pinfunction "P5.7_42") (pintype "passive"))
    )
    (net (code "88") (name "unconnected-(IC1-P5.8-Pad43)") (class "Default")
      (node (ref "IC1") (pin "43") (pinfunction "P5.8_43") (pintype "passive"))
    )
    (net (code "89") (name "unconnected-(IC1-P5.9-Pad44)") (class "Default")
      (node (ref "IC1") (pin "44") (pinfunction "P5.9_44") (pintype "passive"))
    )
    (net (code "90") (name "unconnected-(IC1-P5.10-Pad45)") (class "Default")
      (node (ref "IC1") (pin "45") (pinfunction "P5.10_45") (pintype "passive"))
    )
    (net (code "91") (name "unconnected-(IC1-P5.11-Pad46)") (class "Default")
      (node (ref "IC1") (pin "46") (pinfunction "P5.11_46") (pintype "passive"))
    )
    (net (code "92") (name "unconnected-(IC1-P5.12-Pad47)") (class "Default")
      (node (ref "IC1") (pin "47") (pinfunction "P5.12_47") (pintype "passive"))
    )
    (net (code "93") (name "unconnected-(IC1-P5.13-Pad48)") (class "Default")
      (node (ref "IC1") (pin "48") (pinfunction "P5.13_48") (pintype "passive"))
    )
    (net (code "94") (name "unconnected-(IC1-P5.14-Pad49)") (class "Default")
      (node (ref "IC1") (pin "49") (pinfunction "P5.14_49") (pintype "passive"))
    )
    (net (code "95") (name "unconnected-(IC1-P5.15-Pad50)") (class "Default")
      (node (ref "IC1") (pin "50") (pinfunction "P5.15_50") (pintype "passive"))
    )
    (net (code "96") (name "unconnected-(IC1-P6.0-Pad16)") (class "Default")
      (node (ref "IC1") (pin "16") (pinfunction "P6.0_16") (pintype "passive"))
    )
    (net (code "97") (name "unconnected-(IC1-P6.1-Pad17)") (class "Default")
      (node (ref "IC1") (pin "17") (pinfunction "P6.1_17") (pintype "passive"))
    )
    (net (code "98") (name "unconnected-(IC1-P6.2-Pad18)") (class "Default")
      (node (ref "IC1") (pin "18") (pinfunction "P6.2_18") (pintype "passive"))
    )
    (net (code "99") (name "unconnected-(IC1-P6.3-Pad19)") (class "Default")
      (node (ref "IC1") (pin "19") (pinfunction "P6.3_19") (pintype "passive"))
    )
    (net (code "100") (name "unconnected-(IC1-P7.0-Pad8)") (class "Default")
      (node (ref "IC1") (pin "8") (pinfunction "P7.0_8") (pintype "passive"))
    )
    (net (code "101") (name "unconnected-(IC1-P7.1-Pad11)") (class "Default")
      (node (ref "IC1") (pin "11") (pinfunction "P7.1_11") (pintype "passive"))
    )
    (net (code "102") (name "unconnected-(IC1-P7.2-Pad4)") (class "Default")
      (node (ref "IC1") (pin "4") (pinfunction "P7.2_4") (pintype "passive"))
    )
    (net (code "103") (name "unconnected-(IC1-P8.1-Pad13)") (class "Default")
      (node (ref "IC1") (pin "13") (pinfunction "P8.1_13") (pintype "passive"))
    )
    (net (code "104") (name "unconnected-(IC1-P8.2-Pad10)") (class "Default")
      (node (ref "IC1") (pin "10") (pinfunction "P8.2_10") (pintype "passive"))
    )
    (net (code "105") (name "unconnected-(IC1-P8.3-Pad7)") (class "Default")
      (node (ref "IC1") (pin "7") (pinfunction "P8.3_7") (pintype "passive"))
    )
    (net (code "106") (name "unconnected-(IC1-P8.4-Pad5)") (class "Default")
      (node (ref "IC1") (pin "5") (pinfunction "P8.4_5") (pintype "passive"))
    )
    (net (code "107") (name "unconnected-(IC1-P8.5-Pad143)") (class "Default")
      (node (ref "IC1") (pin "143") (pinfunction "P8.5_143") (pintype "passive"))
    )
    (net (code "108") (name "unconnected-(IC1-P8.6-Pad142)") (class "Default")
      (node (ref "IC1") (pin "142") (pinfunction "P8.6_142") (pintype "passive"))
    )
    (net (code "109") (name "unconnected-(IC1-P9.0-Pad112)") (class "Default")
      (node (ref "IC1") (pin "112") (pinfunction "P9.0_112") (pintype "passive"))
    )
    (net (code "110") (name "unconnected-(IC1-P9.1-Pad114)") (class "Default")
      (node (ref "IC1") (pin "114") (pinfunction "P9.1_114") (pintype "passive"))
    )
    (net (code "111") (name "unconnected-(IC1-P9.2-Pad119)") (class "Default")
      (node (ref "IC1") (pin "119") (pinfunction "P9.2_119") (pintype "passive"))
    )
    (net (code "112") (name "unconnected-(IC1-P9.4-Pad125)") (class "Default")
      (node (ref "IC1") (pin "125") (pinfunction "P9.4_125") (pintype "passive"))
    )
    (net (code "113") (name "unconnected-(IC1-P9.5-Pad126)") (class "Default")
      (node (ref "IC1") (pin "126") (pinfunction "P9.5_126") (pintype "passive"))
    )
    (net (code "114") (name "unconnected-(IC1-P9.6-Pad132)") (class "Default")
      (node (ref "IC1") (pin "132") (pinfunction "P9.6_132") (pintype "passive"))
    )
    (net (code "115") (name "unconnected-(IC1-P9.7-Pad134)") (class "Default")
      (node (ref "IC1") (pin "134") (pinfunction "P9.7_134") (pintype "passive"))
    )
    (net (code "116") (name "unconnected-(IC1-P10.3-Pad95)") (class "Default")
      (node (ref "IC1") (pin "95") (pinfunction "P10.3_95") (pintype "passive"))
    )
    (net (code "117") (name "unconnected-(IC1-P10.4-Pad98)") (class "Default")
      (node (ref "IC1") (pin "98") (pinfunction "P10.4_98") (pintype "passive"))
    )
    (net (code "118") (name "unconnected-(IC1-P10.5-Pad100)") (class "Default")
      (node (ref "IC1") (pin "100") (pinfunction "P10.5_100") (pintype "passive"))
    )
    (net (code "119") (name "unconnected-(IC1-P10.6-Pad103)") (class "Default")
      (node (ref "IC1") (pin "103") (pinfunction "P10.6_103") (pintype "passive"))
    )
    (net (code "120") (name "unconnected-(IC1-P10.7-Pad105)") (class "Default")
      (node (ref "IC1") (pin "105") (pinfunction "P10.7_105") (pintype "passive"))
    )
    (net (code "121") (name "unconnected-(IC1-P10.13-Pad123)") (class "Default")
      (node (ref "IC1") (pin "123") (pinfunction "P10.13_123") (pintype "passive"))
    )
    (net (code "122") (name "unconnected-(IC1-P10.14-Pad128)") (class "Default")
      (node (ref "IC1") (pin "128") (pinfunction "P10.14_128") (pintype "passive"))
    )
    (net (code "123") (name "unconnected-(IC1-P10.15-Pad130)") (class "Default")
      (node (ref "IC1") (pin "130") (pinfunction "P10.15_130") (pintype "passive"))
    )
    (net (code "124") (name "unconnected-(IC1-P11.0-Pad66)") (class "Default")
      (node (ref "IC1") (pin "66") (pinfunction "P11.0_66") (pintype "passive"))
    )
    (net (code "125") (name "unconnected-(IC1-P11.1-Pad65)") (class "Default")
      (node (ref "IC1") (pin "65") (pinfunction "P11.1_65") (pintype "passive"))
    )
    (net (code "126") (name "unconnected-(IC1-P11.2-Pad62)") (class "Default")
      (node (ref "IC1") (pin "62") (pinfunction "P11.2_62") (pintype "passive"))
    )
    (net (code "127") (name "unconnected-(IC1-P11.3-Pad59)") (class "Default")
      (node (ref "IC1") (pin "59") (pinfunction "P11.3_59") (pintype "passive"))
    )
    (net (code "128") (name "unconnected-(IC1-P11.4-Pad57)") (class "Default")
      (node (ref "IC1") (pin "57") (pinfunction "P11.4_57") (pintype "passive"))
    )
    (net (code "129") (name "unconnected-(IC1-P11.5-Pad53)") (class "Default")
      (node (ref "IC1") (pin "53") (pinfunction "P11.5_53") (pintype "passive"))
    )
    (net (code "130") (name "unconnected-(IC1-P15.0-Pad21)") (class "Default")
      (node (ref "IC1") (pin "21") (pinfunction "P15.0_21") (pintype "passive"))
    )
    (net (code "131") (name "unconnected-(IC1-P15.1-Pad22)") (class "Default")
      (node (ref "IC1") (pin "22") (pinfunction "P15.1_22") (pintype "passive"))
    )
    (net (code "132") (name "unconnected-(IC1-P15.2-Pad23)") (class "Default")
      (node (ref "IC1") (pin "23") (pinfunction "P15.2_23") (pintype "passive"))
    )
    (net (code "133") (name "unconnected-(IC1-P15.3-Pad24)") (class "Default")
      (node (ref "IC1") (pin "24") (pinfunction "P15.3_24") (pintype "passive"))
    )
    (net (code "134") (name "unconnected-(IC1-P15.4-Pad25)") (class "Default")
      (node (ref "IC1") (pin "25") (pinfunction "P15.4_25") (pintype "passive"))
    )
    (net (code "135") (name "unconnected-(IC1-P15.5-Pad26)") (class "Default")
      (node (ref "IC1") (pin "26") (pinfunction "P15.5_26") (pintype "passive"))
    )
    (net (code "136") (name "unconnected-(IC1-P15.6-Pad27)") (class "Default")
      (node (ref "IC1") (pin "27") (pinfunction "P15.6_27") (pintype "passive"))
    )
    (net (code "137") (name "unconnected-(IC1-P15.7-Pad28)") (class "Default")
      (node (ref "IC1") (pin "28") (pinfunction "P15.7_28") (pintype "passive"))
    )
    (net (code "138") (name "unconnected-(JP2-Pad17)") (class "Default")
      (node (ref "JP2") (pin "17") (pinfunction "17_17") (pintype "passive"))
    )
    (net (code "139") (name "unconnected-(JP2-Pad18)") (class "Default")
      (node (ref "JP2") (pin "18") (pinfunction "18_18") (pintype "passive"))
    )
    (net (code "140") (name "unconnected-(OCDS-Pad5)") (class "Default")
      (node (ref "OCDS") (pin "5") (pinfunction "5_5") (pintype "passive"))
    )
    (net (code "141") (name "unconnected-(OCDS-Pad14)") (class "Default")
      (node (ref "OCDS") (pin "14") (pinfunction "14_14") (pintype "passive"))
    )
    (net (code "142") (name "unconnected-(OCDS-Pad15)") (class "Default")
      (node (ref "OCDS") (pin "15") (pinfunction "15_15") (pintype "passive"))
    )
    (net (code "143") (name "unconnected-(OCDS-Pad16)") (class "Default")
      (node (ref "OCDS") (pin "16") (pinfunction "16_16") (pintype "passive"))
    )
  )
)
